# Sheet1.net
KiCad netlist of a schematic drawn in Altium Designer
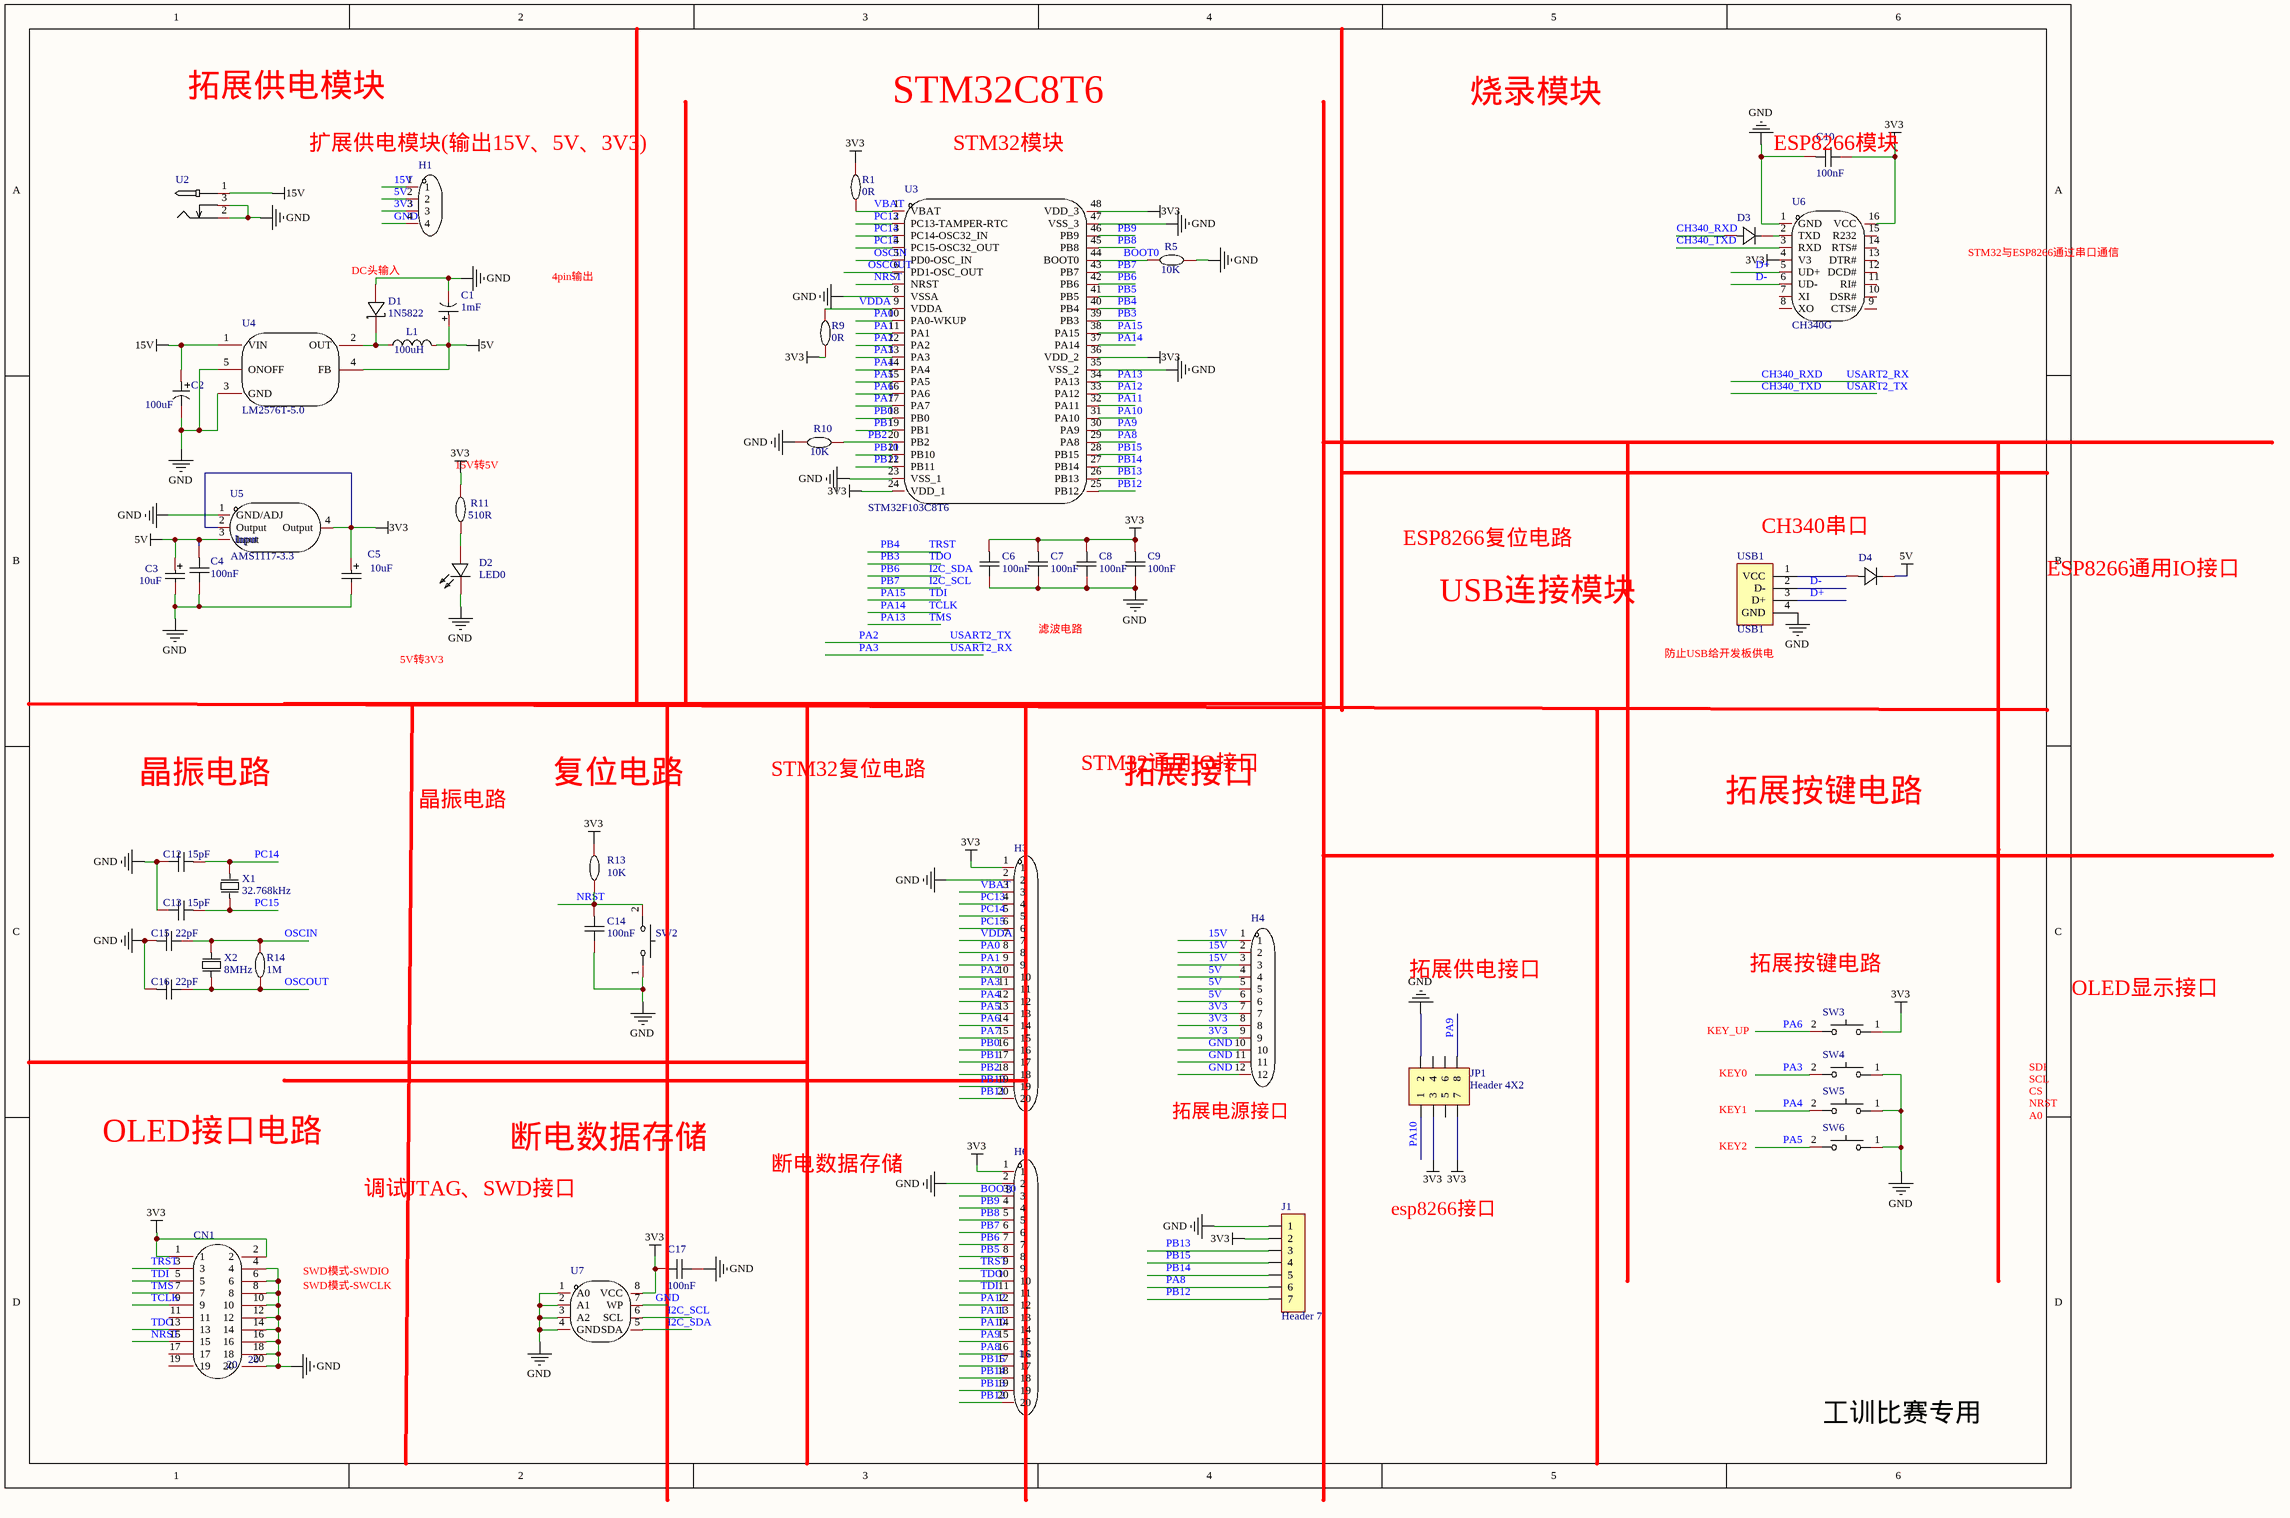
[diagram p0: Sheet1.SchDoc]

(export (version "E")
  (design (tool "Eeschema 10.0.6"))
  (components
    (comp (ref "C1")
      (value "1mF")
      (footprint "CM D8(6.3*7.7)")
      (description "容值:1mF;精度:±20%;额定电压:25V;电容体直径:10mm;电容体长度:20mm;脚间距:5mm;工作寿命:7000hrs@105;")
      (fields
        (field (name "MANUFACTURER") "SAMYOUNG(韩国三莹)")
        (field (name "MANUFACTURER PART") "NXA25VB1000M 10*20 LO")
      )
      (libsource (lib "altium-import") (part "root_1_NXA25VB1000M 10*20 LO_"))
    )
    (comp (ref "C2")
      (value "100uF")
      (footprint "CM F(8*10.2)")
      (description "容值:100uF;额定电压:50V;电容体直径:-;电容体长度:-;纹波电流:-;等效串联电阻:-;工作寿命:-;")
      (fields
        (field (name "MANUFACTURER") "KNSCHA(科尼盛)")
        (field (name "MANUFACTURER PART") "XT100UF50V90RV0067")
      )
      (libsource (lib "altium-import") (part "root_3_XT100UF50V90RV0067_"))
    )
    (comp (ref "C3")
      (value "10uF")
      (footprint "CASE-A_3216")
      (description "额定电压:10V;等效串联电阻:8Ω 100kHz;工作温度:-55~+125;容值:10uF;精度:±10%;")
      (fields
        (field (name "MANUFACTURER") "CEC(振华新云)")
        (field (name "MANUFACTURER PART") "CA45-A-10V-10uF-K")
      )
      (libsource (lib "altium-import") (part "root_3_CA45-A-10V-10uF-K_"))
    )
    (comp (ref "C4")
      (value "100nF")
      (footprint "0603_C")
      (fields (field (name "Comment") "CAP_0603"))
      (libsource (lib "altium-import") (part "root_1_CAP_0603_"))
    )
    (comp (ref "C5")
      (value "10uF")
      (footprint "CASE-A_3216")
      (description "额定电压:10V;等效串联电阻:8Ω 100kHz;工作温度:-55~+125;容值:10uF;精度:±10%;")
      (fields
        (field (name "MANUFACTURER") "CEC(振华新云)")
        (field (name "MANUFACTURER PART") "CA45-A-10V-10uF-K")
      )
      (libsource (lib "altium-import") (part "root_3_CA45-A-10V-10uF-K_"))
    )
    (comp (ref "C6")
      (value "100nF")
      (footprint "0603_C")
      (fields (field (name "Comment") "CAP_0603"))
      (libsource (lib "altium-import") (part "root_1_CAP_0603_"))
    )
    (comp (ref "C7")
      (value "100nF")
      (footprint "0603_C")
      (fields (field (name "Comment") "CAP_0603"))
      (libsource (lib "altium-import") (part "root_1_CAP_0603_"))
    )
    (comp (ref "C8")
      (value "100nF")
      (footprint "0603_C")
      (fields (field (name "Comment") "CAP_0603"))
      (libsource (lib "altium-import") (part "root_1_CAP_0603_"))
    )
    (comp (ref "C9")
      (value "100nF")
      (footprint "0603_C")
      (fields (field (name "Comment") "CAP_0603"))
      (libsource (lib "altium-import") (part "root_1_CAP_0603_"))
    )
    (comp (ref "C10")
      (value "100nF")
      (footprint "0603_C")
      (fields (field (name "Comment") "CAP_0603"))
      (libsource (lib "altium-import") (part "root_2_CAP_0603_"))
    )
    (comp (ref "C12")
      (value "15pF")
      (footprint "0603_C")
      (fields (field (name "Comment") "CAP_0603"))
      (libsource (lib "altium-import") (part "root_0_CAP_0603_"))
    )
    (comp (ref "C13")
      (value "15pF")
      (footprint "0603_C")
      (fields (field (name "Comment") "CAP_0603"))
      (libsource (lib "altium-import") (part "root_0_CAP_0603_"))
    )
    (comp (ref "C14")
      (value "100nF")
      (footprint "0603_C")
      (fields (field (name "Comment") "CAP_0603"))
      (libsource (lib "altium-import") (part "root_1_CAP_0603_"))
    )
    (comp (ref "C15")
      (value "22pF")
      (footprint "0603_C")
      (fields (field (name "Comment") "CAP_0603"))
      (libsource (lib "altium-import") (part "root_2_CAP_0603_"))
    )
    (comp (ref "C16")
      (value "22pF")
      (footprint "0603_C")
      (fields (field (name "Comment") "CAP_0603"))
      (libsource (lib "altium-import") (part "root_2_CAP_0603_"))
    )
    (comp (ref "C17")
      (value "100nF")
      (footprint "0603_C")
      (fields (field (name "Comment") "CAP_0603"))
      (libsource (lib "altium-import") (part "root_2_CAP_0603_"))
    )
    (comp (ref "CN1")
      (value "HX30002-20A")
      (footprint "DC-2.54-L-Z-20P")
      (description "参考系列:-;间距:3mm;插针结构:2x10P;排数:2;每排PIN数:10;行距:3mm;安装方式:-;触头材质:黄铜;")
      (fields (field (name "MANUFACTURER") "HX(红星)") (field (name "NAME") "20") (field (name "NUMBER") "20"))
      (libsource (lib "altium-import") (part "root_0_HX30002-20A_"))
    )
    (comp (ref "D1")
      (value "1N5822")
      (footprint "SMA(DO-214AC)")
      (description "直流反向耐压(Vr):40V;平均整流电流(Io):3A;正向压降(Vf):525mV@3A;")
      (fields (field (name "NAME") "1N5822") (field (name "MANUFACTURER") "星海"))
      (libsource (lib "altium-import") (part "root_1_1N5822_"))
    )
    (comp (ref "D2")
      (value "25-21/GHC-YSU/2A")
      (footprint "LED 0603R")
      (fields (field (name "NAME") "LED0") (field (name "MANUFACTURER") "EVERLIGHT(亿光)"))
      (libsource (lib "altium-import") (part "root_1_25-21/GHC-YSU/2A_"))
    )
    (comp (ref "D3")
      (value "1N4007")
      (footprint "SOD-323")
      (description "二极管配置:-;直流反向耐压(Vr):1kV;平均整流电流(Io):1A;正向压降(Vf):1.1V@1A;反向电流(Ir):5A@1kV;")
      (libsource (lib "altium-import") (part "root_0_1N4007_"))
    )
    (comp (ref "D4")
      (value "1N4007")
      (footprint "SOD-323")
      (description "二极管配置:-;直流反向耐压(Vr):1kV;平均整流电流(Io):1A;正向压降(Vf):1.1V@1A;反向电流(Ir):5A@1kV;")
      (libsource (lib "altium-import") (part "root_0_1N4007_"))
    )
    (comp (ref "H1")
      (value "HDR-M_2.54_1x4P")
      (footprint "HDR2.54-LI-4P")
      (libsource (lib "altium-import") (part "root_0_HDR-M_2.54_1x4P_"))
    )
    (comp (ref "H3")
      (value "HDR-M_2.54_1x20P")
      (footprint "HDR2.54-LI-20P")
      (libsource (lib "altium-import") (part "root_0_HDR-M_2.54_1x20P_"))
    )
    (comp (ref "H4")
      (value "HDR-M_2.54_1x12P")
      (footprint "HDR2.54-LI-12P")
      (libsource (lib "altium-import") (part "root_0_HDR-M_2.54_1x12P_"))
    )
    (comp (ref "H6")
      (value "HDR-M_2.54_1x20P")
      (footprint "HDR2.54-LI-20P")
      (fields (field (name "NAME") "16") (field (name "NUMBER") "3"))
      (libsource (lib "altium-import") (part "root_0_HDR-M_2.54_1x20P_"))
    )
    (comp (ref "J1")
      (value "Header 7")
      (footprint "HDR2.54-LI-7P")
      (description "J  Header, 7-Pin")
      (fields (field (name "PUBLISHER") "Altium Limited"))
      (libsource (lib "7连接器") (part "Header 7"))
    )
    (comp (ref "JP1")
      (value "Header 4X2")
      (footprint "HDR2.54-LI-2x4P")
      (description "J  Header, 4-Pin, Dual row")
      (fields (field (name "PUBLISHER") "Altium Limited"))
      (libsource (lib "7连接器") (part "Header 4X2"))
    )
    (comp (ref "L1")
      (value "100uH")
      (footprint "CDRH127")
      (description "电感值:100uH;精度:±10%;额定电流:730mA;饱和电流(Isat):-;直流电阻(DCR):325mΩ;")
      (fields (field (name "MANUFACTURER") "SHOU HAN(首韩)") (field (name "MANUFACTURER PART") "CY75-100UH"))
      (libsource (lib "altium-import") (part "root_0_CY75-100UH_"))
    )
    (comp (ref "R1")
      (value "0R")
      (footprint "0603_R")
      (description "阻值:0Ω;精度:-;功率:-;工作温度范围:-55~+155;")
      (fields (field (name "MANUFACTURER") "KOA") (field (name "MANUFACTURER PART") "RK73Z2BTTD"))
      (libsource (lib "altium-import") (part "root_1_RK73Z2BTTD_"))
    )
    (comp (ref "R5")
      (value "10K")
      (footprint "0603_R")
      (fields (field (name "Comment") "Res_0603"))
      (libsource (lib "altium-import") (part "root_0_Res_0603_"))
    )
    (comp (ref "R9")
      (value "0R")
      (footprint "0603_R")
      (fields (field (name "Comment") "Res_0603"))
      (libsource (lib "altium-import") (part "root_1_Res_0603_"))
    )
    (comp (ref "R10")
      (value "10K")
      (footprint "0603_R")
      (fields (field (name "Comment") "Res_0603"))
      (libsource (lib "altium-import") (part "root_0_Res_0603_"))
    )
    (comp (ref "R11")
      (value "510R")
      (footprint "0603_R")
      (fields (field (name "Comment") "Res_0603"))
      (libsource (lib "altium-import") (part "root_1_Res_0603_"))
    )
    (comp (ref "R13")
      (value "10K")
      (footprint "0603_R")
      (fields (field (name "Comment") "Res_0603"))
      (libsource (lib "altium-import") (part "root_1_Res_0603_"))
    )
    (comp (ref "R14")
      (value "1M")
      (footprint "0603_R")
      (fields (field (name "Comment") "Res_0603"))
      (libsource (lib "altium-import") (part "root_1_Res_0603_"))
    )
    (comp (ref "SW2")
      (value "SW-74-3")
      (footprint "TSW SMD-3*6*2.5")
      (fields (field (name "MANUFACTURER") "Shinmei(日本神明)"))
      (libsource (lib "altium-import") (part "root_3_SW-74-3_"))
    )
    (comp (ref "SW3")
      (value "SW-74-3")
      (footprint "TSW SMD-3*6*2.5")
      (fields (field (name "MANUFACTURER") "Shinmei(日本神明)"))
      (libsource (lib "") (part "root_0_SW-74-3__1"))
    )
    (comp (ref "SW4")
      (value "SW-74-3")
      (footprint "TSW SMD-3*6*2.5")
      (fields (field (name "MANUFACTURER") "Shinmei(日本神明)"))
      (libsource (lib "altium-import") (part "root_0_SW-74-3_"))
    )
    (comp (ref "SW5")
      (value "SW-74-3")
      (footprint "TSW SMD-3*6*2.5")
      (fields (field (name "MANUFACTURER") "Shinmei(日本神明)"))
      (libsource (lib "altium-import") (part "root_0_SW-74-3_"))
    )
    (comp (ref "SW6")
      (value "SW-74-3")
      (footprint "TSW SMD-3*6*2.5")
      (fields (field (name "MANUFACTURER") "Shinmei(日本神明)"))
      (libsource (lib "altium-import") (part "root_0_SW-74-3_"))
    )
    (comp (ref "U2")
      (value "DC-210_DC母座,板上插件3P,2mm,黑壳")
      (footprint "DC-005")
      (libsource (lib "altium-import") (part "root_0_DC-210_DC母座,板上插件3P,2mm,黑壳_"))
    )
    (comp (ref "U3")
      (value "STM32F103C8T6")
      (footprint "LQFP48 7X7_N")
      (fields (field (name "NAME") "STM32F103C8T6") (field (name "MANUFACTURER") "ST(意法半导体)"))
      (libsource (lib "altium-import") (part "root_0_STM32F103C8T6_"))
    )
    (comp (ref "U4")
      (value "LM2576T-5.0/NOPB")
      (footprint "TO-263-5")
      (description "功能类型:降压型;同步整流:-;输出通道数:-;拓扑结构:-;输入电压:-;输出电流(最大值):-;开关频率:-;")
      (fields (field (name "NAME") "LM2576T-5.0") (field (name "MANUFACTURER") "TI(德州仪器)"))
      (libsource (lib "altium-import") (part "root_0_LM2576T-5.0/NOPB_"))
    )
    (comp (ref "U5")
      (value "AMS1117-3.3_C369933")
      (footprint "SOT-223")
      (fields
        (field (name "NAME") "AMS1117-3.3")
        (field (name "MANUFACTURER") "KEXIN(科信)")
        (field (name "MANUFACTURER PART") "AMS1117-3.3")
        (field (name "NAME_1") "Input")
      )
      (libsource (lib "altium-import") (part "root_0_AMS1117-3.3_C369933_"))
    )
    (comp (ref "U6")
      (value "CH340G")
      (footprint "SOP-16_150mil")
      (description "类型:Transceiver;协议类别:USB 2.0;驱动器/接收器数:-;数据速率:2Mbps;")
      (fields (field (name "NAME") "CH340G") (field (name "MANUFACTURER") "WCH(南京沁恒)"))
      (libsource (lib "altium-import") (part "root_0_CH340G_"))
    )
    (comp (ref "U7")
      (value "AT24C04M/TR")
      (footprint "SOP-8_150mil")
      (description "存储器类型:-;存储器容量:-;存储器接口类型:-;工作电压:-;")
      (fields (field (name "MANUFACTURER") "HGSEMI(华冠)"))
      (libsource (lib "altium-import") (part "root_0_AT24C04M/TR_"))
    )
    (comp (ref "USB1")
      (value "USB1")
      (footprint "USB-A/S_A")
      (description "J  USB接口")
      (libsource (lib "7-1USB-DB-RJ45-SD-HDMI") (part "USB1"))
    )
    (comp (ref "X1")
      (value "32.768kHz")
      (footprint "OSC 3215-2P")
      (description "晶振类型:-;频率:32.768kHz;频率公差:±20ppm;频率稳定度:-;负载电容:12.5pF;等效串联电阻(ESR):90kΩ;工作温度:-40~+85;")
      (fields (field (name "MANUFACTURER") "ABRACON") (field (name "MANUFACTURER PART") "ABS06-32.768KHZ-T"))
      (libsource (lib "altium-import") (part "root_1_ABS06-32.768KHZ-T_"))
    )
    (comp (ref "X2")
      (value "8MHz")
      (footprint "HC-49SMD")
      (description "晶振类型:49SMD;频率:8MHz;频率公差:±30ppm;频率稳定度:±50ppm;负载电容:20pF;等效串联电阻(ESR):-;工作温度:-40~+85;")
      (fields
        (field (name "MANUFACTURER") "HCI(杭晶)")
        (field (name "MANUFACTURER PART") "X49SS2-8.000-F20JGDT")
      )
      (libsource (lib "altium-import") (part "root_1_X49SS2-8.000-F20JGDT_"))
    )
  )
  (nets
    (net (code "1") (name "/BOOT0") (class "Default")
      (node (ref "H6") (pin "3") (pinfunction "3_3") (pintype "passive"))
      (node (ref "R5") (pin "1") (pinfunction "1_1") (pintype "passive"))
      (node (ref "U3") (pin "44") (pinfunction "BOOT0_44") (pintype "passive"))
    )
    (net (code "2") (name "/CH340_RXD") (class "Default")
      (node (ref "D3") (pin "1") (pinfunction "A_1") (pintype "passive"))
      (node (ref "H3") (pin "11") (pinfunction "11_11") (pintype "passive"))
      (node (ref "SW4") (pin "2") (pinfunction "2_2") (pintype "passive"))
      (node (ref "U3") (pin "13") (pinfunction "PA3_13") (pintype "passive"))
    )
    (net (code "3") (name "/CH340_TXD") (class "Default")
      (node (ref "H3") (pin "10") (pinfunction "10_10") (pintype "passive"))
      (node (ref "U3") (pin "12") (pinfunction "PA2_12") (pintype "passive"))
      (node (ref "U6") (pin "3") (pinfunction "RXD_3") (pintype "passive"))
    )
    (net (code "4") (name "/D+") (class "Default")
      (node (ref "U6") (pin "5") (pinfunction "UD+_5") (pintype "passive"))
      (node (ref "USB1") (pin "3") (pinfunction "D+_3") (pintype "passive"))
    )
    (net (code "5") (name "/D-") (class "Default")
      (node (ref "U6") (pin "6") (pinfunction "UD-_6") (pintype "passive"))
      (node (ref "USB1") (pin "2") (pinfunction "D-_2") (pintype "passive"))
    )
    (net (code "6") (name "/I2C_SCL") (class "Default")
      (node (ref "H6") (pin "6") (pinfunction "6_6") (pintype "passive"))
      (node (ref "U3") (pin "43") (pinfunction "PB7_43") (pintype "passive"))
      (node (ref "U7") (pin "6") (pinfunction "SCL_6") (pintype "passive"))
    )
    (net (code "7") (name "/I2C_SDA") (class "Default")
      (node (ref "H6") (pin "7") (pinfunction "7_7") (pintype "passive"))
      (node (ref "U3") (pin "42") (pinfunction "PB6_42") (pintype "passive"))
      (node (ref "U7") (pin "5") (pinfunction "SDA_5") (pintype "passive"))
    )
    (net (code "8") (name "/NRST") (class "Default")
      (node (ref "C14") (pin "2") (pinfunction "2_2") (pintype "passive"))
      (node (ref "CN1") (pin "15") (pinfunction "15_15") (pintype "passive"))
      (node (ref "R13") (pin "1") (pinfunction "1_1") (pintype "passive"))
      (node (ref "SW2") (pin "2") (pinfunction "2_2") (pintype "passive"))
      (node (ref "U3") (pin "7") (pinfunction "NRST_7") (pintype "passive"))
    )
    (net (code "9") (name "/OSCIN") (class "Default")
      (node (ref "C15") (pin "1") (pinfunction "1_1") (pintype "passive"))
      (node (ref "R14") (pin "2") (pinfunction "2_2") (pintype "passive"))
      (node (ref "U3") (pin "5") (pinfunction "PD0-OSC_IN_5") (pintype "passive"))
      (node (ref "X2") (pin "2") (pinfunction "OSC2_2") (pintype "passive"))
    )
    (net (code "10") (name "/OSCOUT") (class "Default")
      (node (ref "C16") (pin "1") (pinfunction "1_1") (pintype "passive"))
      (node (ref "R14") (pin "1") (pinfunction "1_1") (pintype "passive"))
      (node (ref "U3") (pin "6") (pinfunction "PD1-OSC_OUT_6") (pintype "passive"))
      (node (ref "X2") (pin "1") (pinfunction "OSC1_1") (pintype "passive"))
    )
    (net (code "11") (name "/PA0") (class "Default")
      (node (ref "H3") (pin "8") (pinfunction "8_8") (pintype "passive"))
      (node (ref "U3") (pin "10") (pinfunction "PA0-WKUP_10") (pintype "passive"))
    )
    (net (code "12") (name "/PA1") (class "Default")
      (node (ref "H3") (pin "9") (pinfunction "9_9") (pintype "passive"))
      (node (ref "U3") (pin "11") (pinfunction "PA1_11") (pintype "passive"))
    )
    (net (code "13") (name "/PA4") (class "Default")
      (node (ref "H3") (pin "12") (pinfunction "12_12") (pintype "passive"))
      (node (ref "SW5") (pin "2") (pinfunction "2_2") (pintype "passive"))
      (node (ref "U3") (pin "14") (pinfunction "PA4_14") (pintype "passive"))
    )
    (net (code "14") (name "/PA5") (class "Default")
      (node (ref "H3") (pin "13") (pinfunction "13_13") (pintype "passive"))
      (node (ref "SW6") (pin "2") (pinfunction "2_2") (pintype "passive"))
      (node (ref "U3") (pin "15") (pinfunction "PA5_15") (pintype "passive"))
    )
    (net (code "15") (name "/PA6") (class "Default")
      (node (ref "H3") (pin "14") (pinfunction "14_14") (pintype "passive"))
      (node (ref "SW3") (pin "2") (pinfunction "2_2") (pintype "passive"))
      (node (ref "U3") (pin "16") (pinfunction "PA6_16") (pintype "passive"))
    )
    (net (code "16") (name "/PA7") (class "Default")
      (node (ref "H3") (pin "15") (pinfunction "15_15") (pintype "passive"))
      (node (ref "U3") (pin "17") (pinfunction "PA7_17") (pintype "passive"))
    )
    (net (code "17") (name "/PA8") (class "Default")
      (node (ref "H6") (pin "16") (pinfunction "16_16") (pintype "passive"))
      (node (ref "J1") (pin "6") (pinfunction "6_6") (pintype "passive"))
      (node (ref "U3") (pin "29") (pinfunction "PA8_29") (pintype "passive"))
    )
    (net (code "18") (name "/PA9") (class "Default")
      (node (ref "H6") (pin "15") (pinfunction "15_15") (pintype "passive"))
      (node (ref "JP1") (pin "8") (pinfunction "8_8") (pintype "passive"))
      (node (ref "U3") (pin "30") (pinfunction "PA9_30") (pintype "passive"))
    )
    (net (code "19") (name "/PA10") (class "Default")
      (node (ref "H6") (pin "14") (pinfunction "14_14") (pintype "passive"))
      (node (ref "JP1") (pin "1") (pinfunction "1_1") (pintype "passive"))
      (node (ref "U3") (pin "31") (pinfunction "PA10_31") (pintype "passive"))
    )
    (net (code "20") (name "/PA11") (class "Default")
      (node (ref "H6") (pin "13") (pinfunction "13_13") (pintype "passive"))
      (node (ref "U3") (pin "32") (pinfunction "PA11_32") (pintype "passive"))
    )
    (net (code "21") (name "/PA12") (class "Default")
      (node (ref "H6") (pin "12") (pinfunction "12_12") (pintype "passive"))
      (node (ref "U3") (pin "33") (pinfunction "PA12_33") (pintype "passive"))
    )
    (net (code "22") (name "/PA13") (class "Default")
      (node (ref "CN1") (pin "7") (pinfunction "7_7") (pintype "passive"))
      (node (ref "U3") (pin "34") (pinfunction "PA13_34") (pintype "passive"))
    )
    (net (code "23") (name "/PA14") (class "Default")
      (node (ref "CN1") (pin "9") (pinfunction "9_9") (pintype "passive"))
      (node (ref "U3") (pin "37") (pinfunction "PA14_37") (pintype "passive"))
    )
    (net (code "24") (name "/PA15") (class "Default")
      (node (ref "CN1") (pin "5") (pinfunction "5_5") (pintype "passive"))
      (node (ref "H6") (pin "11") (pinfunction "11_11") (pintype "passive"))
      (node (ref "U3") (pin "38") (pinfunction "PA15_38") (pintype "passive"))
    )
    (net (code "25") (name "/PB0") (class "Default")
      (node (ref "H3") (pin "16") (pinfunction "16_16") (pintype "passive"))
      (node (ref "U3") (pin "18") (pinfunction "PB0_18") (pintype "passive"))
    )
    (net (code "26") (name "/PB1") (class "Default")
      (node (ref "H3") (pin "17") (pinfunction "17_17") (pintype "passive"))
      (node (ref "U3") (pin "19") (pinfunction "PB1_19") (pintype "passive"))
    )
    (net (code "27") (name "/PB2") (class "Default")
      (node (ref "H3") (pin "18") (pinfunction "18_18") (pintype "passive"))
      (node (ref "R10") (pin "2") (pinfunction "2_2") (pintype "passive"))
      (node (ref "U3") (pin "20") (pinfunction "PB2_20") (pintype "passive"))
    )
    (net (code "28") (name "/PB3") (class "Default")
      (node (ref "CN1") (pin "13") (pinfunction "13_13") (pintype "passive"))
      (node (ref "H6") (pin "10") (pinfunction "10_10") (pintype "passive"))
      (node (ref "U3") (pin "39") (pinfunction "PB3_39") (pintype "passive"))
    )
    (net (code "29") (name "/PB4") (class "Default")
      (node (ref "CN1") (pin "3") (pinfunction "3_3") (pintype "passive"))
      (node (ref "H6") (pin "9") (pinfunction "9_9") (pintype "passive"))
      (node (ref "U3") (pin "40") (pinfunction "PB4_40") (pintype "passive"))
    )
    (net (code "30") (name "/PB5") (class "Default")
      (node (ref "H6") (pin "8") (pinfunction "8_8") (pintype "passive"))
      (node (ref "U3") (pin "41") (pinfunction "PB5_41") (pintype "passive"))
    )
    (net (code "31") (name "/PB8") (class "Default")
      (node (ref "H6") (pin "5") (pinfunction "5_5") (pintype "passive"))
      (node (ref "U3") (pin "45") (pinfunction "PB8_45") (pintype "passive"))
    )
    (net (code "32") (name "/PB9") (class "Default")
      (node (ref "H6") (pin "4") (pinfunction "4_4") (pintype "passive"))
      (node (ref "U3") (pin "46") (pinfunction "PB9_46") (pintype "passive"))
    )
    (net (code "33") (name "/PB10") (class "Default")
      (node (ref "H3") (pin "19") (pinfunction "19_19") (pintype "passive"))
      (node (ref "U3") (pin "21") (pinfunction "PB10_21") (pintype "passive"))
    )
    (net (code "34") (name "/PB11") (class "Default")
      (node (ref "H3") (pin "20") (pinfunction "20_20") (pintype "passive"))
      (node (ref "U3") (pin "22") (pinfunction "PB11_22") (pintype "passive"))
    )
    (net (code "35") (name "/PB12") (class "Default")
      (node (ref "H6") (pin "20") (pinfunction "20_20") (pintype "passive"))
      (node (ref "J1") (pin "7") (pinfunction "7_7") (pintype "passive"))
      (node (ref "U3") (pin "25") (pinfunction "PB12_25") (pintype "passive"))
    )
    (net (code "36") (name "/PB13") (class "Default")
      (node (ref "H6") (pin "19") (pinfunction "19_19") (pintype "passive"))
      (node (ref "J1") (pin "3") (pinfunction "3_3") (pintype "passive"))
      (node (ref "U3") (pin "26") (pinfunction "PB13_26") (pintype "passive"))
    )
    (net (code "37") (name "/PB14") (class "Default")
      (node (ref "H6") (pin "18") (pinfunction "18_18") (pintype "passive"))
      (node (ref "J1") (pin "5") (pinfunction "5_5") (pintype "passive"))
      (node (ref "U3") (pin "27") (pinfunction "PB14_27") (pintype "passive"))
    )
    (net (code "38") (name "/PB15") (class "Default")
      (node (ref "H6") (pin "17") (pinfunction "17_17") (pintype "passive"))
      (node (ref "J1") (pin "4") (pinfunction "4_4") (pintype "passive"))
      (node (ref "U3") (pin "28") (pinfunction "PB15_28") (pintype "passive"))
    )
    (net (code "39") (name "/PC13") (class "Default")
      (node (ref "H3") (pin "4") (pinfunction "4_4") (pintype "passive"))
      (node (ref "U3") (pin "2") (pinfunction "PC13-TAMPER-RTC_2") (pintype "passive"))
    )
    (net (code "40") (name "/PC14") (class "Default")
      (node (ref "C12") (pin "2") (pinfunction "2_2") (pintype "passive"))
      (node (ref "H3") (pin "5") (pinfunction "5_5") (pintype "passive"))
      (node (ref "U3") (pin "3") (pinfunction "PC14-OSC32_IN_3") (pintype "passive"))
      (node (ref "X1") (pin "2") (pinfunction "OSC2_2") (pintype "passive"))
    )
    (net (code "41") (name "/PC15") (class "Default")
      (node (ref "C13") (pin "2") (pinfunction "2_2") (pintype "passive"))
      (node (ref "H3") (pin "6") (pinfunction "6_6") (pintype "passive"))
      (node (ref "U3") (pin "4") (pinfunction "PC15-OSC32_OUT_4") (pintype "passive"))
      (node (ref "X1") (pin "1") (pinfunction "OSC1_1") (pintype "passive"))
    )
    (net (code "42") (name "/VBAT") (class "Default")
      (node (ref "H3") (pin "3") (pinfunction "3_3") (pintype "passive"))
      (node (ref "R1") (pin "1") (pinfunction "1_1") (pintype "passive"))
      (node (ref "U3") (pin "1") (pinfunction "VBAT_1") (pintype "passive"))
    )
    (net (code "43") (name "/VDDA") (class "Default")
      (node (ref "H3") (pin "7") (pinfunction "7_7") (pintype "passive"))
      (node (ref "R9") (pin "2") (pinfunction "2_2") (pintype "passive"))
      (node (ref "U3") (pin "9") (pinfunction "VDDA_9") (pintype "passive"))
    )
    (net (code "44") (name "3V3") (class "Default")
      (node (ref "C10") (pin "1") (pinfunction "1_1") (pintype "passive"))
      (node (ref "C17") (pin "2") (pinfunction "2_2") (pintype "passive"))
      (node (ref "C5") (pin "1") (pinfunction "1_1") (pintype "passive"))
      (node (ref "C6") (pin "2") (pinfunction "2_2") (pintype "passive"))
      (node (ref "C7") (pin "2") (pinfunction "2_2") (pintype "passive"))
      (node (ref "C8") (pin "2") (pinfunction "2_2") (pintype "passive"))
      (node (ref "C9") (pin "2") (pinfunction "2_2") (pintype "passive"))
      (node (ref "CN1") (pin "1") (pinfunction "1_1") (pintype "passive"))
      (node (ref "CN1") (pin "2") (pinfunction "2_2") (pintype "passive"))
      (node (ref "H1") (pin "3") (pinfunction "3_3") (pintype "passive"))
      (node (ref "H3") (pin "1") (pinfunction "1_1") (pintype "passive"))
      (node (ref "H4") (pin "7") (pinfunction "7_7") (pintype "passive"))
      (node (ref "H4") (pin "8") (pinfunction "8_8") (pintype "passive"))
      (node (ref "H4") (pin "9") (pinfunction "9_9") (pintype "passive"))
      (node (ref "H6") (pin "1") (pinfunction "1_1") (pintype "passive"))
      (node (ref "J1") (pin "2") (pinfunction "2_2") (pintype "passive"))
      (node (ref "JP1") (pin "3") (pinfunction "3_3") (pintype "passive"))
      (node (ref "JP1") (pin "7") (pinfunction "7_7") (pintype "passive"))
      (node (ref "R1") (pin "2") (pinfunction "2_2") (pintype "passive"))
      (node (ref "R11") (pin "2") (pinfunction "2_2") (pintype "passive"))
      (node (ref "R13") (pin "2") (pinfunction "2_2") (pintype "passive"))
      (node (ref "R9") (pin "1") (pinfunction "1_1") (pintype "passive"))
      (node (ref "SW3") (pin "1") (pinfunction "1_1") (pintype "passive"))
      (node (ref "U3") (pin "24") (pinfunction "VDD_1_24") (pintype "passive"))
      (node (ref "U3") (pin "36") (pinfunction "VDD_2_36") (pintype "passive"))
      (node (ref "U3") (pin "48") (pinfunction "VDD_3_48") (pintype "passive"))
      (node (ref "U5") (pin "2") (pinfunction "Output_2") (pintype "passive"))
      (node (ref "U5") (pin "4") (pinfunction "Output_4") (pintype "passive"))
      (node (ref "U6") (pin "16") (pinfunction "VCC_16") (pintype "passive"))
      (node (ref "U6") (pin "4") (pinfunction "V3_4") (pintype "passive"))
      (node (ref "U7") (pin "8") (pinfunction "VCC_8") (pintype "passive"))
    )
    (net (code "45") (name "5V") (class "Default")
      (node (ref "C1") (pin "1") (pinfunction "1_1") (pintype "passive"))
      (node (ref "C3") (pin "1") (pinfunction "1_1") (pintype "passive"))
      (node (ref "C4") (pin "2") (pinfunction "2_2") (pintype "passive"))
      (node (ref "D4") (pin "2") (pinfunction "K_2") (pintype "passive"))
      (node (ref "H1") (pin "2") (pinfunction "2_2") (pintype "passive"))
      (node (ref "H4") (pin "4") (pinfunction "4_4") (pintype "passive"))
      (node (ref "H4") (pin "5") (pinfunction "5_5") (pintype "passive"))
      (node (ref "H4") (pin "6") (pinfunction "6_6") (pintype "passive"))
      (node (ref "L1") (pin "2") (pinfunction "2_2") (pintype "passive"))
      (node (ref "U4") (pin "4") (pinfunction "FB_4") (pintype "passive"))
      (node (ref "U5") (pin "3") (pinfunction "Input_3") (pintype "passive"))
    )
    (net (code "46") (name "15V") (class "Default")
      (node (ref "C2") (pin "1") (pinfunction "1_1") (pintype "passive"))
      (node (ref "H1") (pin "1") (pinfunction "1_1") (pintype "passive"))
      (node (ref "H4") (pin "1") (pinfunction "1_1") (pintype "passive"))
      (node (ref "H4") (pin "2") (pinfunction "2_2") (pintype "passive"))
      (node (ref "H4") (pin "3") (pinfunction "3_3") (pintype "passive"))
      (node (ref "U2") (pin "1") (pinfunction "1_1") (pintype "passive"))
      (node (ref "U4") (pin "1") (pinfunction "VIN_1") (pintype "passive"))
    )
    (net (code "47") (name "GND") (class "Default")
      (node (ref "C1") (pin "2") (pinfunction "2_2") (pintype "passive"))
      (node (ref "C10") (pin "2") (pinfunction "2_2") (pintype "passive"))
      (node (ref "C12") (pin "1") (pinfunction "1_1") (pintype "passive"))
      (node (ref "C13") (pin "1") (pinfunction "1_1") (pintype "passive"))
      (node (ref "C14") (pin "1") (pinfunction "1_1") (pintype "passive"))
      (node (ref "C15") (pin "2") (pinfunction "2_2") (pintype "passive"))
      (node (ref "C16") (pin "2") (pinfunction "2_2") (pintype "passive"))
      (node (ref "C17") (pin "1") (pinfunction "1_1") (pintype "passive"))
      (node (ref "C2") (pin "2") (pinfunction "2_2") (pintype "passive"))
      (node (ref "C3") (pin "2") (pinfunction "2_2") (pintype "passive"))
      (node (ref "C4") (pin "1") (pinfunction "1_1") (pintype "passive"))
      (node (ref "C5") (pin "2") (pinfunction "2_2") (pintype "passive"))
      (node (ref "C6") (pin "1") (pinfunction "1_1") (pintype "passive"))
      (node (ref "C7") (pin "1") (pinfunction "1_1") (pintype "passive"))
      (node (ref "C8") (pin "1") (pinfunction "1_1") (pintype "passive"))
      (node (ref "C9") (pin "1") (pinfunction "1_1") (pintype "passive"))
      (node (ref "CN1") (pin "10") (pinfunction "10_10") (pintype "passive"))
      (node (ref "CN1") (pin "12") (pinfunction "12_12") (pintype "passive"))
      (node (ref "CN1") (pin "14") (pinfunction "14_14") (pintype "passive"))
      (node (ref "CN1") (pin "16") (pinfunction "16_16") (pintype "passive"))
      (node (ref "CN1") (pin "18") (pinfunction "18_18") (pintype "passive"))
      (node (ref "CN1") (pin "20") (pinfunction "20_20") (pintype "passive"))
      (node (ref "CN1") (pin "4") (pinfunction "4_4") (pintype "passive"))
      (node (ref "CN1") (pin "6") (pinfunction "6_6") (pintype "passive"))
      (node (ref "CN1") (pin "8") (pinfunction "8_8") (pintype "passive"))
      (node (ref "D1") (pin "2") (pinfunction "A_2") (pintype "passive"))
      (node (ref "D2") (pin "2") (pinfunction "K_2") (pintype "passive"))
      (node (ref "H1") (pin "4") (pinfunction "4_4") (pintype "passive"))
      (node (ref "H3") (pin "2") (pinfunction "2_2") (pintype "passive"))
      (node (ref "H4") (pin "10") (pinfunction "10_10") (pintype "passive"))
      (node (ref "H4") (pin "11") (pinfunction "11_11") (pintype "passive"))
      (node (ref "H4") (pin "12") (pinfunction "12_12") (pintype "passive"))
      (node (ref "H6") (pin "2") (pinfunction "2_2") (pintype "passive"))
      (node (ref "J1") (pin "1") (pinfunction "1_1") (pintype "passive"))
      (node (ref "JP1") (pin "2") (pinfunction "2_2") (pintype "passive"))
      (node (ref "R10") (pin "1") (pinfunction "1_1") (pintype "passive"))
      (node (ref "R5") (pin "2") (pinfunction "2_2") (pintype "passive"))
      (node (ref "SW2") (pin "1") (pinfunction "1_1") (pintype "passive"))
      (node (ref "SW4") (pin "1") (pinfunction "1_1") (pintype "passive"))
      (node (ref "SW5") (pin "1") (pinfunction "1_1") (pintype "passive"))
      (node (ref "SW6") (pin "1") (pinfunction "1_1") (pintype "passive"))
      (node (ref "U2") (pin "2") (pinfunction "2_2") (pintype "passive"))
      (node (ref "U2") (pin "3") (pinfunction "3_3") (pintype "passive"))
      (node (ref "U3") (pin "23") (pinfunction "VSS_1_23") (pintype "passive"))
      (node (ref "U3") (pin "35") (pinfunction "VSS_2_35") (pintype "passive"))
      (node (ref "U3") (pin "47") (pinfunction "VSS_3_47") (pintype "passive"))
      (node (ref "U3") (pin "8") (pinfunction "VSSA_8") (pintype "passive"))
      (node (ref "U4") (pin "3") (pinfunction "GND_3") (pintype "passive"))
      (node (ref "U4") (pin "5") (pinfunction "ONOFF_5") (pintype "passive"))
      (node (ref "U5") (pin "1") (pinfunction "GND/ADJ_1") (pintype "passive"))
      (node (ref "U6") (pin "1") (pinfunction "GND_1") (pintype "passive"))
      (node (ref "U7") (pin "1") (pinfunction "A0_1") (pintype "passive"))
      (node (ref "U7") (pin "2") (pinfunction "A1_2") (pintype "passive"))
      (node (ref "U7") (pin "3") (pinfunction "A2_3") (pintype "passive"))
      (node (ref "U7") (pin "4") (pinfunction "GND_4") (pintype "passive"))
      (node (ref "U7") (pin "7") (pinfunction "WP_7") (pintype "passive"))
      (node (ref "USB1") (pin "4") (pinfunction "GND_4") (pintype "passive"))
    )
    (net (code "48") (name "Net-(D1-C)") (class "Default")
      (node (ref "D1") (pin "1") (pinfunction "C_1") (pintype "passive"))
      (node (ref "L1") (pin "1") (pinfunction "1_1") (pintype "passive"))
      (node (ref "U4") (pin "2") (pinfunction "OUT_2") (pintype "passive"))
    )
    (net (code "49") (name "Net-(D2-A)") (class "Default")
      (node (ref "D2") (pin "1") (pinfunction "A_1") (pintype "passive"))
      (node (ref "R11") (pin "1") (pinfunction "1_1") (pintype "passive"))
    )
    (net (code "50") (name "Net-(D3-K)") (class "Default")
      (node (ref "D3") (pin "2") (pinfunction "K_2") (pintype "passive"))
      (node (ref "U6") (pin "2") (pinfunction "TXD_2") (pintype "passive"))
    )
    (net (code "51") (name "Net-(D4-A)") (class "Default")
      (node (ref "D4") (pin "1") (pinfunction "A_1") (pintype "passive"))
      (node (ref "USB1") (pin "1") (pinfunction "VCC_1") (pintype "passive"))
    )
    (net (code "52") (name "unconnected-(CN1-Pad11)") (class "Default")
      (node (ref "CN1") (pin "11") (pinfunction "11_11") (pintype "passive"))
    )
    (net (code "53") (name "unconnected-(CN1-Pad17)") (class "Default")
      (node (ref "CN1") (pin "17") (pinfunction "17_17") (pintype "passive"))
    )
    (net (code "54") (name "unconnected-(CN1-Pad19)") (class "Default")
      (node (ref "CN1") (pin "19") (pinfunction "19_19") (pintype "passive"))
    )
    (net (code "55") (name "unconnected-(JP1-Pad4)") (class "Default")
      (node (ref "JP1") (pin "4") (pinfunction "4_4") (pintype "passive"))
    )
    (net (code "56") (name "unconnected-(JP1-Pad5)") (class "Default")
      (node (ref "JP1") (pin "5") (pinfunction "5_5") (pintype "passive"))
    )
    (net (code "57") (name "unconnected-(JP1-Pad6)") (class "Default")
      (node (ref "JP1") (pin "6") (pinfunction "6_6") (pintype "passive"))
    )
    (net (code "58") (name "unconnected-(U6-CTS#-Pad9)") (class "Default")
      (node (ref "U6") (pin "9") (pinfunction "CTS#_9") (pintype "passive"))
    )
    (net (code "59") (name "unconnected-(U6-DCD#-Pad12)") (class "Default")
      (node (ref "U6") (pin "12") (pinfunction "DCD#_12") (pintype "passive"))
    )
    (net (code "60") (name "unconnected-(U6-DSR#-Pad10)") (class "Default")
      (node (ref "U6") (pin "10") (pinfunction "DSR#_10") (pintype "passive"))
    )
    (net (code "61") (name "unconnected-(U6-DTR#-Pad13)") (class "Default")
      (node (ref "U6") (pin "13") (pinfunction "DTR#_13") (pintype "passive"))
    )
    (net (code "62") (name "unconnected-(U6-R232-Pad15)") (class "Default")
      (node (ref "U6") (pin "15") (pinfunction "R232_15") (pintype "passive"))
    )
    (net (code "63") (name "unconnected-(U6-RI#-Pad11)") (class "Default")
      (node (ref "U6") (pin "11") (pinfunction "RI#_11") (pintype "passive"))
    )
    (net (code "64") (name "unconnected-(U6-RTS#-Pad14)") (class "Default")
      (node (ref "U6") (pin "14") (pinfunction "RTS#_14") (pintype "passive"))
    )
    (net (code "65") (name "unconnected-(U6-XI-Pad7)") (class "Default")
      (node (ref "U6") (pin "7") (pinfunction "XI_7") (pintype "passive"))
    )
    (net (code "66") (name "unconnected-(U6-XO-Pad8)") (class "Default")
      (node (ref "U6") (pin "8") (pinfunction "XO_8") (pintype "passive"))
    )
  )
)
